# Sht5-V12P0_Jetson.net
KiCad netlist of a schematic drawn in Altium Designer
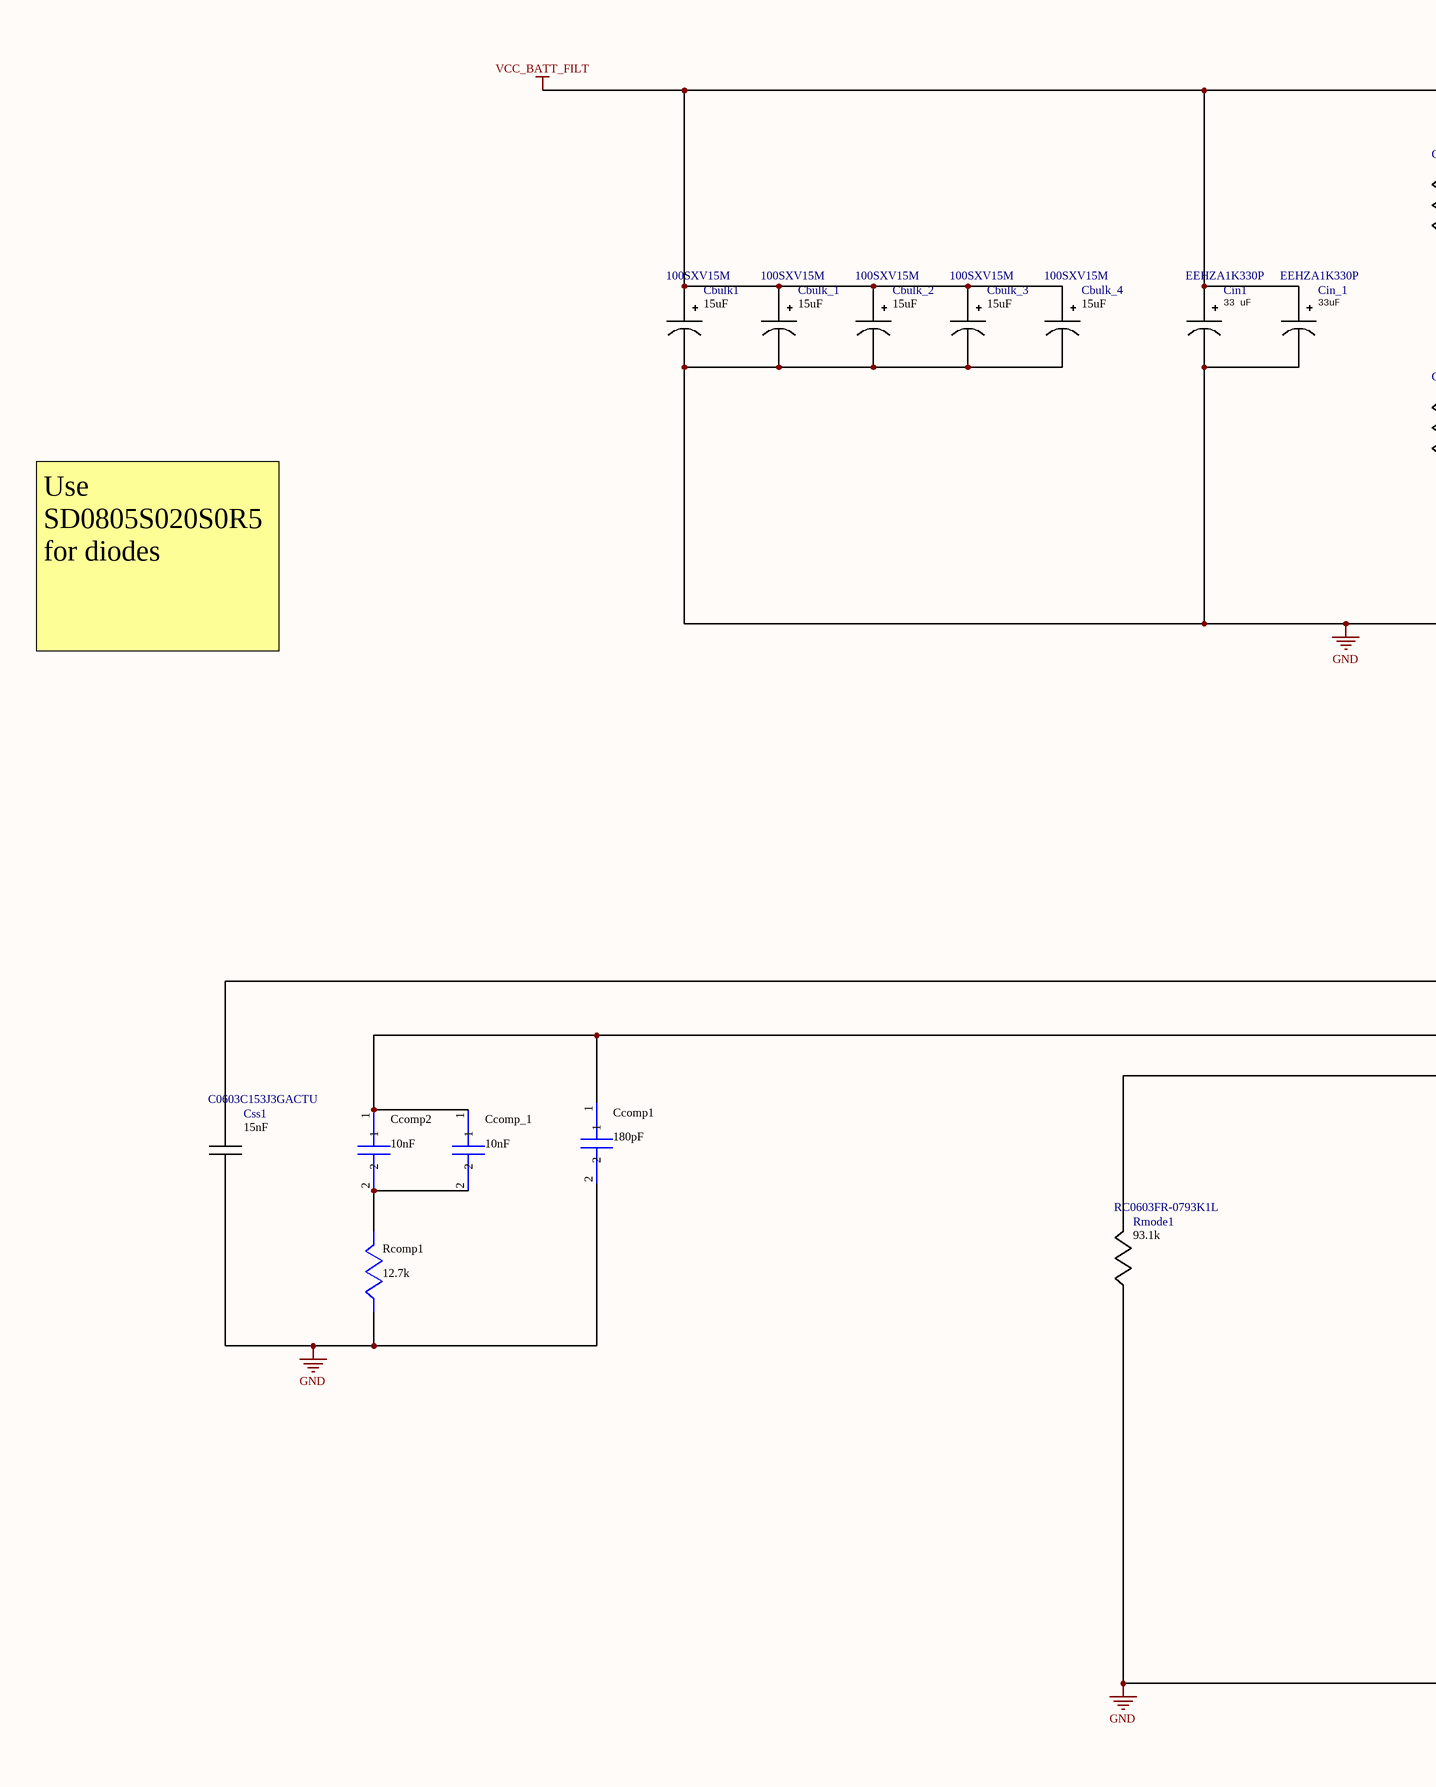
[diagram p0: Sht5-V12P0_Jetson.SchDoc, left]
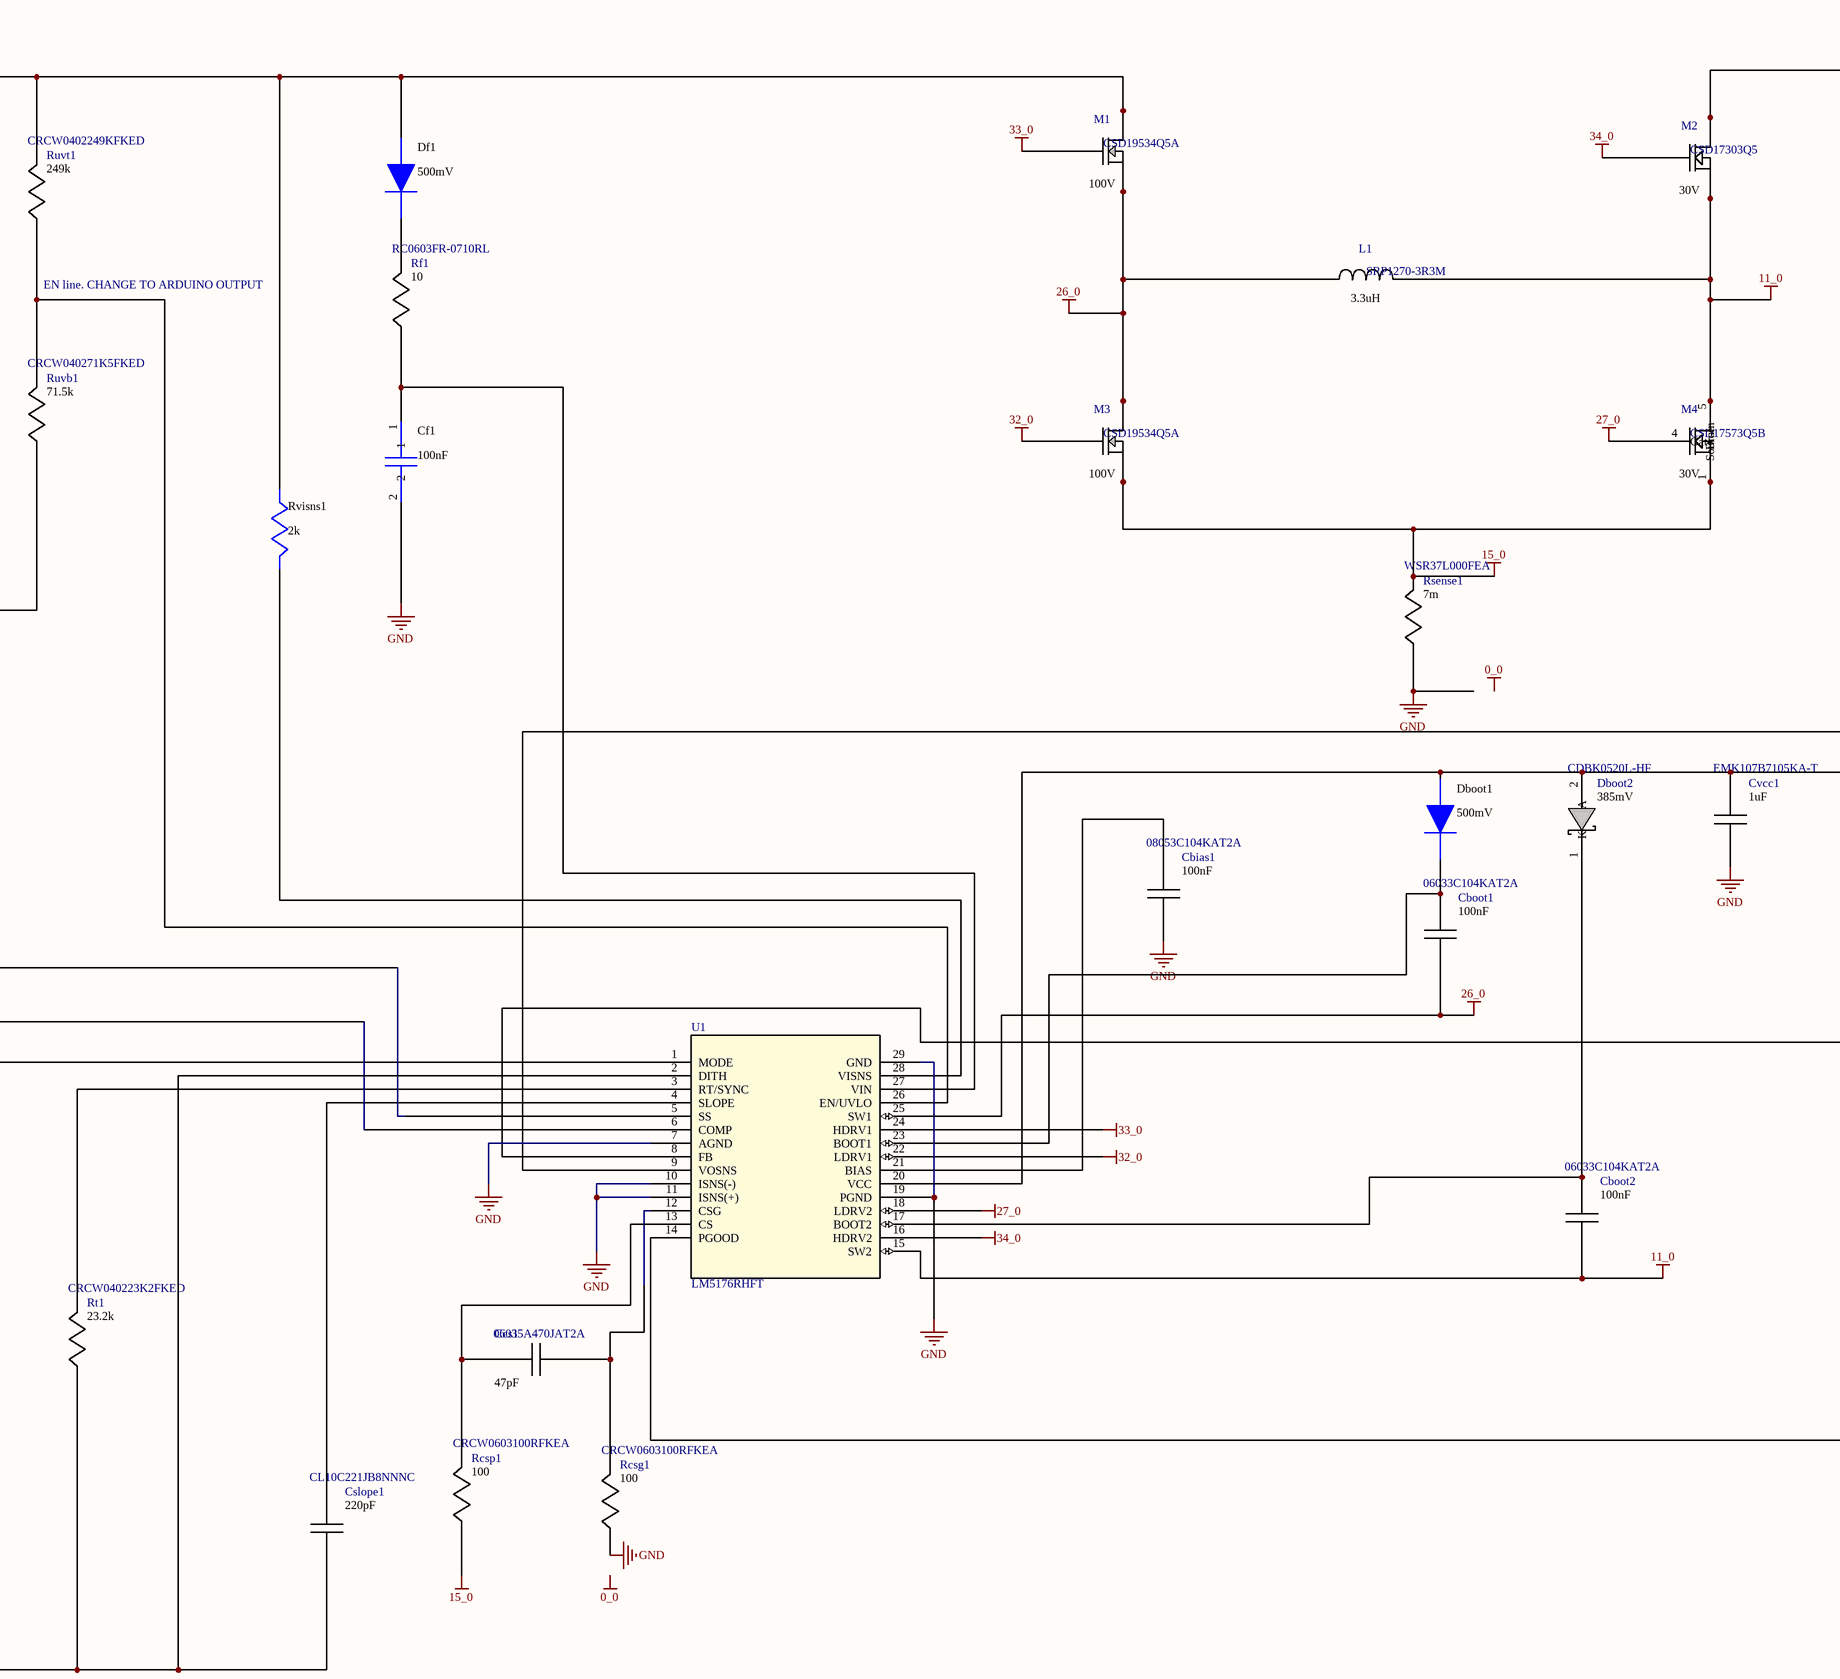
[diagram p1: Sht5-V12P0_Jetson.SchDoc, middle]
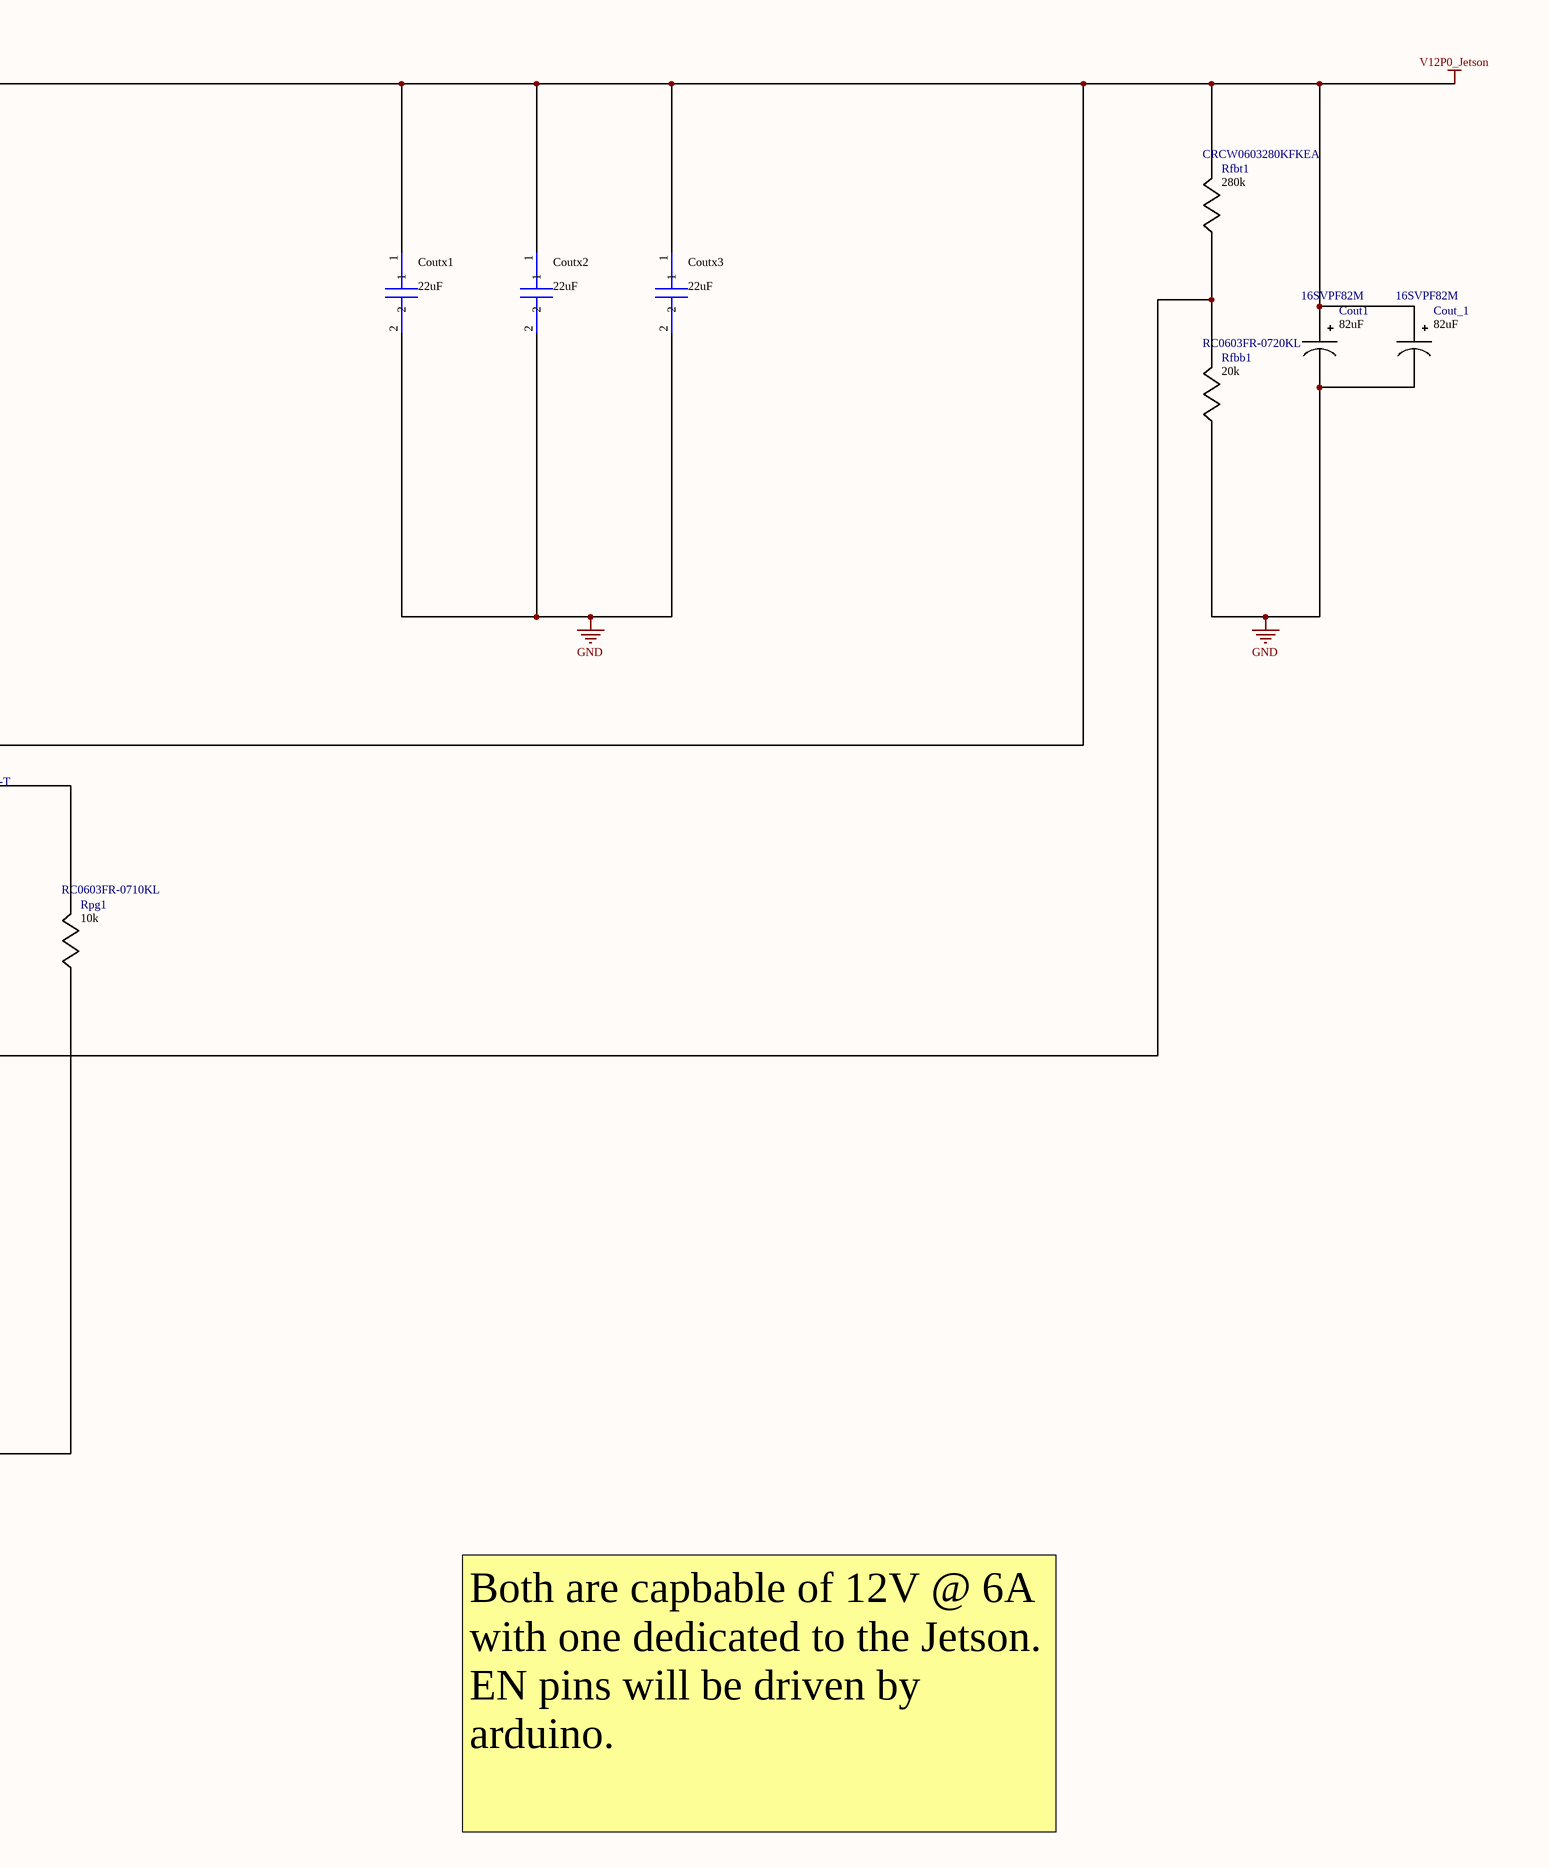
[diagram p2: Sht5-V12P0_Jetson.SchDoc, right]

(export (version "E")
  (design (tool "Eeschema 10.0.6"))
  (components
    (comp (ref "Cbias1")
      (value "08053C104KAT2A")
      (footprint "0805")
      (fields (field (name "ALTIUM_VALUE") "100nF"))
      (libsource (lib "TAUV-Lib") (part "08053C104KAT2A"))
    )
    (comp (ref "Cboot1")
      (value "06033C104KAT2A")
      (footprint "0603")
      (fields (field (name "ALTIUM_VALUE") "100nF"))
      (libsource (lib "TAUV-Lib") (part "06033C104KAT2A"))
    )
    (comp (ref "Cboot2")
      (value "06033C104KAT2A")
      (footprint "0603")
      (fields (field (name "ALTIUM_VALUE") "100nF"))
      (libsource (lib "TAUV-Lib") (part "06033C104KAT2A"))
    )
    (comp (ref "Cbulk1")
      (value "100SXV15M")
      (footprint "CAPSMT_62_E12")
      (fields (field (name "ALTIUM_VALUE") "15uF"))
      (libsource (lib "TAUV-Lib") (part "100SXV15M"))
    )
    (comp (ref "Cbulk_1")
      (value "100SXV15M")
      (footprint "CAPSMT_62_E12")
      (fields (field (name "ALTIUM_VALUE") "15uF"))
      (libsource (lib "TAUV-Lib") (part "100SXV15M"))
    )
    (comp (ref "Cbulk_2")
      (value "100SXV15M")
      (footprint "CAPSMT_62_E12")
      (fields (field (name "ALTIUM_VALUE") "15uF"))
      (libsource (lib "TAUV-Lib") (part "100SXV15M"))
    )
    (comp (ref "Cbulk_3")
      (value "100SXV15M")
      (footprint "CAPSMT_62_E12")
      (fields (field (name "ALTIUM_VALUE") "15uF"))
      (libsource (lib "TAUV-Lib") (part "100SXV15M"))
    )
    (comp (ref "Cbulk_4")
      (value "100SXV15M")
      (footprint "CAPSMT_62_E12")
      (fields (field (name "ALTIUM_VALUE") "15uF"))
      (libsource (lib "TAUV-Lib") (part "100SXV15M"))
    )
    (comp (ref "Ccomp1")
      (value "180pF")
      (footprint "0805")
      (description "C0805C181K5GACTU")
      (libsource (lib "TAUV-Lib") (part "Ccomp2"))
    )
    (comp (ref "Ccomp2")
      (value "10nF")
      (footprint "0402")
      (description "CGA2B3X7R1H103K0")
      (fields (field (name "MANUFACTURER PART NUMBER") "CGA2B3X7R1H103K050BB"))
      (libsource (lib "TAUV-Lib") (part "Ccomp"))
    )
    (comp (ref "Ccomp_1")
      (value "10nF")
      (footprint "0402")
      (description "CGA2B3X7R1H103K0")
      (fields (field (name "MANUFACTURER PART NUMBER") "CGA2B3X7R1H103K050BB"))
      (libsource (lib "TAUV-Lib") (part "Ccomp_2"))
    )
    (comp (ref "Ccs1")
      (value "06035A470JAT2A")
      (footprint "0603")
      (fields (field (name "ALTIUM_VALUE") "47pF"))
      (libsource (lib "TAUV-Lib") (part "06035A470JAT2A"))
    )
    (comp (ref "Cf1")
      (value "100nF")
      (footprint "0603")
      (description "CGA3E2X7R1H104K0")
      (fields (field (name "MANUFACTURER PART NUMBER") "CGA3E2X7R1H104K080AA"))
      (libsource (lib "TAUV-Lib") (part "Cf"))
    )
    (comp (ref "Cin1")
      (value "EEHZA1K330P")
      (footprint "SM_RADIAL_10BMM")
      (description "No Description Available")
      (fields
        (field (name "ALTIUM_VALUE") "33 uF")
        (field (name "COPYRIGHT") "Copyright (C) 2018 Accelerated Designs. All rights reserved")
      )
      (libsource (lib "TAUV-Lib") (part "EEHZA1K330P"))
    )
    (comp (ref "Cin_1")
      (value "EEHZA1K330P")
      (footprint "SM_RADIAL_10BMM")
      (description "No Description Available")
      (fields
        (field (name "ALTIUM_VALUE") "33uF")
        (field (name "COPYRIGHT") "Copyright (C) 2018 Accelerated Designs. All rights reserved")
      )
      (libsource (lib "TAUV-Lib") (part "EEHZA1K330P"))
    )
    (comp (ref "Cout1")
      (value "16SVPF82M")
      (footprint "CAPSMT_62_E61")
      (fields (field (name "ALTIUM_VALUE") "82uF"))
      (libsource (lib "TAUV-Lib") (part "16SVPF82M"))
    )
    (comp (ref "Coutx1")
      (value "22uF")
      (footprint "0805")
      (description "C2012X5R1V226M12")
      (fields (field (name "MANUFACTURER PART NUMBER") "C2012X5R1V226M125AC"))
      (libsource (lib "TAUV-Lib") (part "Coutx"))
    )
    (comp (ref "Coutx2")
      (value "22uF")
      (footprint "0805")
      (description "C2012X5R1V226M12")
      (fields (field (name "MANUFACTURER PART NUMBER") "C2012X5R1V226M125AC"))
      (libsource (lib "TAUV-Lib") (part "Coutx2"))
    )
    (comp (ref "Coutx3")
      (value "22uF")
      (footprint "0805")
      (description "C2012X5R1V226M12")
      (fields (field (name "MANUFACTURER PART NUMBER") "C2012X5R1V226M125AC"))
      (libsource (lib "TAUV-Lib") (part "Coutx3"))
    )
    (comp (ref "Cout_1")
      (value "16SVPF82M")
      (footprint "CAPSMT_62_E61")
      (fields (field (name "ALTIUM_VALUE") "82uF"))
      (libsource (lib "TAUV-Lib") (part "16SVPF82M"))
    )
    (comp (ref "Cslope1")
      (value "CL10C221JB8NNNC")
      (footprint "0603")
      (fields (field (name "ALTIUM_VALUE") "220pF"))
      (libsource (lib "TAUV-Lib") (part "CL10C221JB8NNNC"))
    )
    (comp (ref "Css1")
      (value "C0603C153J3GACTU")
      (footprint "0603")
      (fields (field (name "ALTIUM_VALUE") "15nF"))
      (libsource (lib "TAUV-Lib") (part "C0603C153J3GACTU"))
    )
    (comp (ref "Cvcc1")
      (value "EMK107B7105KA-T")
      (footprint "0603")
      (fields (field (name "ALTIUM_VALUE") "1uF"))
      (libsource (lib "TAUV-Lib") (part "EMK107B7105KA-T"))
    )
    (comp (ref "Dboot1")
      (value "500mV")
      (footprint "GEN_Diode")
      (description "CUSTOM1")
      (fields (field (name "MANUFACTURER PART NUMBER") "GENERIC_DIODE"))
      (libsource (lib "TAUV-Lib") (part "Dboot1"))
    )
    (comp (ref "Dboot2")
      (value "CDBK0520L-HF")
      (footprint "SOD-123F")
      (fields (field (name "ALTIUM_VALUE") "385mV"))
      (libsource (lib "TAUV-Lib") (part "CDBK0520L-HF"))
    )
    (comp (ref "Df1")
      (value "500mV")
      (footprint "GEN_Diode")
      (description "CUSTOM2")
      (fields (field (name "MANUFACTURER PART NUMBER") "GENERIC_DIODE"))
      (libsource (lib "TAUV-Lib") (part "Df"))
    )
    (comp (ref "L1")
      (value "SRP1270-3R3M")
      (footprint "SRP1270")
      (fields (field (name "ALTIUM_VALUE") "3.3uH"))
      (libsource (lib "TAUV-Lib") (part "SRP1270-3R3M"))
    )
    (comp (ref "M1")
      (value "CSD19534Q5A")
      (footprint "TRANS_NexFET_Q5A")
      (fields (field (name "ALTIUM_VALUE") "100V"))
      (libsource (lib "TAUV-Lib") (part "CSD19534Q5A"))
    )
    (comp (ref "M2")
      (value "CSD17303Q5")
      (footprint "TRANS_NexFET_Q5")
      (fields (field (name "ALTIUM_VALUE") "30V"))
      (libsource (lib "TAUV-Lib") (part "CSD17303Q5"))
    )
    (comp (ref "M3")
      (value "CSD19534Q5A")
      (footprint "TRANS_NexFET_Q5A")
      (fields (field (name "ALTIUM_VALUE") "100V"))
      (libsource (lib "TAUV-Lib") (part "CSD19534Q5A"))
    )
    (comp (ref "M4")
      (value "CSD17573Q5B")
      (footprint "DNK0008A")
      (description "CSD17573Q5B- Note out of stock, double check available subs")
      (fields (field (name "ALTIUM_VALUE") "30V"))
      (libsource (lib "TAUV-Lib") (part "CSD17573Q5B"))
    )
    (comp (ref "Rcomp1")
      (value "12.7k")
      (footprint "0402")
      (description "CRCW040212K7FKED")
      (libsource (lib "TAUV-Lib") (part "Rcomp"))
    )
    (comp (ref "Rcsg1")
      (value "CRCW0603100RFKEA")
      (footprint "0603")
      (fields (field (name "ALTIUM_VALUE") "100"))
      (libsource (lib "TAUV-Lib") (part "CRCW0603100RFKEA"))
    )
    (comp (ref "Rcsp1")
      (value "CRCW0603100RFKEA")
      (footprint "0603")
      (fields (field (name "ALTIUM_VALUE") "100"))
      (libsource (lib "TAUV-Lib") (part "CRCW0603100RFKEA"))
    )
    (comp (ref "Rf1")
      (value "RC0603FR-0710RL")
      (footprint "0603")
      (fields (field (name "ALTIUM_VALUE") "10"))
      (libsource (lib "TAUV-Lib") (part "RC0603FR-0710RL"))
    )
    (comp (ref "Rfbb1")
      (value "RC0603FR-0720KL")
      (footprint "0603")
      (fields (field (name "ALTIUM_VALUE") "20k"))
      (libsource (lib "TAUV-Lib") (part "RC0603FR-0720KL"))
    )
    (comp (ref "Rfbt1")
      (value "CRCW0603280KFKEA")
      (footprint "0603")
      (fields (field (name "ALTIUM_VALUE") "280k"))
      (libsource (lib "TAUV-Lib") (part "CRCW0603280KFKEA"))
    )
    (comp (ref "Rmode1")
      (value "RC0603FR-0793K1L")
      (footprint "0603")
      (fields (field (name "ALTIUM_VALUE") "93.1k"))
      (libsource (lib "TAUV-Lib") (part "RC0603FR-0793K1L"))
    )
    (comp (ref "Rpg1")
      (value "RC0603FR-0710KL")
      (footprint "0603")
      (fields (field (name "ALTIUM_VALUE") "10k"))
      (libsource (lib "TAUV-Lib") (part "RC0603FR-0710KL"))
    )
    (comp (ref "Rsense1")
      (value "WSR37L000FEA")
      (footprint "4527")
      (fields (field (name "ALTIUM_VALUE") "7m"))
      (libsource (lib "TAUV-Lib") (part "WSR37L000FEA"))
    )
    (comp (ref "Rt1")
      (value "CRCW040223K2FKED")
      (footprint "0402")
      (fields (field (name "ALTIUM_VALUE") "23.2k"))
      (libsource (lib "TAUV-Lib") (part "CRCW040223K2FKED"))
    )
    (comp (ref "Ruvb1")
      (value "CRCW040271K5FKED")
      (footprint "0402")
      (fields (field (name "ALTIUM_VALUE") "71.5k"))
      (libsource (lib "TAUV-Lib") (part "CRCW040271K5FKED"))
    )
    (comp (ref "Ruvt1")
      (value "CRCW0402249KFKED")
      (footprint "0402")
      (fields (field (name "ALTIUM_VALUE") "249k"))
      (libsource (lib "TAUV-Lib") (part "CRCW0402249KFKED"))
    )
    (comp (ref "Rvisns1")
      (value "2k")
      (footprint "0603")
      (description "CRCW06032K00FKEA")
      (libsource (lib "TAUV-Lib") (part "Rvisns"))
    )
    (comp (ref "U1")
      (value "LM5176RHFT")
      (footprint "VQFN_76RHFT_TEX")
      (description "No Description Available")
      (fields (field (name "COPYRIGHT") "Copyright (C) 2022 Ultra Librarian. All rights reserved."))
      (libsource (lib "TAUV-Lib") (part "LM5176RHFT"))
    )
  )
  (nets
    (net (code "2") (name "11_0") (class "Default")
      (node (ref "Cboot2") (pin "2") (pinfunction "2_2") (pintype "passive"))
      (node (ref "L1") (pin "2") (pinfunction "2_2") (pintype "passive"))
      (node (ref "M2") (pin "1") (pinfunction "Source_1") (pintype "passive"))
      (node (ref "M2") (pin "2") (pinfunction "Source_2") (pintype "passive"))
      (node (ref "M2") (pin "3") (pinfunction "Source_3") (pintype "passive"))
      (node (ref "M4") (pin "5") (pinfunction "Drain_5") (pintype "passive"))
      (node (ref "M4") (pin "6") (pinfunction "Drain_6") (pintype "passive"))
      (node (ref "M4") (pin "7") (pinfunction "Drain_7") (pintype "passive"))
      (node (ref "M4") (pin "8") (pinfunction "Drain_8") (pintype "passive"))
      (node (ref "M4") (pin "9") (pinfunction "Drain_9") (pintype "passive"))
      (node (ref "U1") (pin "15") (pinfunction "SW2_15") (pintype "bidirectional"))
    )
    (net (code "3") (name "15_0") (class "Default")
      (node (ref "M3") (pin "1") (pinfunction "Source_1") (pintype "passive"))
      (node (ref "M3") (pin "2") (pinfunction "Source_2") (pintype "passive"))
      (node (ref "M3") (pin "3") (pinfunction "Source_3") (pintype "passive"))
      (node (ref "M4") (pin "1") (pinfunction "Source_1") (pintype "passive"))
      (node (ref "M4") (pin "2") (pinfunction "Source_2") (pintype "passive"))
      (node (ref "M4") (pin "3") (pinfunction "Source_3") (pintype "passive"))
      (node (ref "Rcsp1") (pin "2") (pinfunction "2_2") (pintype "passive"))
      (node (ref "Rsense1") (pin "1") (pinfunction "1_1") (pintype "passive"))
    )
    (net (code "4") (name "26_0") (class "Default")
      (node (ref "Cboot1") (pin "2") (pinfunction "2_2") (pintype "passive"))
      (node (ref "L1") (pin "1") (pinfunction "1_1") (pintype "passive"))
      (node (ref "M1") (pin "1") (pinfunction "Source_1") (pintype "passive"))
      (node (ref "M1") (pin "2") (pinfunction "Source_2") (pintype "passive"))
      (node (ref "M1") (pin "3") (pinfunction "Source_3") (pintype "passive"))
      (node (ref "M3") (pin "5") (pinfunction "Drain_5") (pintype "passive"))
      (node (ref "M3") (pin "6") (pinfunction "Drain_6") (pintype "passive"))
      (node (ref "M3") (pin "7") (pinfunction "Drain_7") (pintype "passive"))
      (node (ref "M3") (pin "8") (pinfunction "Drain_8") (pintype "passive"))
      (node (ref "M3") (pin "9") (pinfunction "Drain_9") (pintype "passive"))
      (node (ref "U1") (pin "25") (pinfunction "SW1_25") (pintype "bidirectional"))
    )
    (net (code "5") (name "27_0") (class "Default")
      (node (ref "M4") (pin "4") (pinfunction "Gate_4") (pintype "passive"))
      (node (ref "U1") (pin "18") (pinfunction "LDRV2_18") (pintype "bidirectional"))
    )
    (net (code "6") (name "32_0") (class "Default")
      (node (ref "M3") (pin "4") (pinfunction "Gate_4") (pintype "passive"))
      (node (ref "U1") (pin "22") (pinfunction "LDRV1_22") (pintype "bidirectional"))
    )
    (net (code "7") (name "33_0") (class "Default")
      (node (ref "M1") (pin "4") (pinfunction "Gate_4") (pintype "passive"))
      (node (ref "U1") (pin "24") (pinfunction "HDRV1_24") (pintype "passive"))
    )
    (net (code "8") (name "34_0") (class "Default")
      (node (ref "M2") (pin "4") (pinfunction "Gate_4") (pintype "passive"))
      (node (ref "U1") (pin "16") (pinfunction "HDRV2_16") (pintype "passive"))
    )
    (net (code "9") (name "GND") (class "Default")
      (node (ref "Cbias1") (pin "2") (pinfunction "2_2") (pintype "passive"))
      (node (ref "Cbulk1") (pin "2") (pinfunction "-_2") (pintype "passive"))
      (node (ref "Cbulk_1") (pin "2") (pinfunction "-_2") (pintype "passive"))
      (node (ref "Cbulk_2") (pin "2") (pinfunction "-_2") (pintype "passive"))
      (node (ref "Cbulk_3") (pin "2") (pinfunction "-_2") (pintype "passive"))
      (node (ref "Cbulk_4") (pin "2") (pinfunction "-_2") (pintype "passive"))
      (node (ref "Ccomp1") (pin "2") (pinfunction "2_2") (pintype "passive"))
      (node (ref "Cf1") (pin "2") (pinfunction "2_2") (pintype "passive"))
      (node (ref "Cin1") (pin "2") (pinfunction "-_2") (pintype "passive"))
      (node (ref "Cin_1") (pin "2") (pinfunction "-_2") (pintype "passive"))
      (node (ref "Cout1") (pin "2") (pinfunction "-_2") (pintype "passive"))
      (node (ref "Cout_1") (pin "2") (pinfunction "-_2") (pintype "passive"))
      (node (ref "Coutx1") (pin "2") (pinfunction "2_2") (pintype "passive"))
      (node (ref "Coutx2") (pin "2") (pinfunction "2_2") (pintype "passive"))
      (node (ref "Coutx3") (pin "2") (pinfunction "2_2") (pintype "passive"))
      (node (ref "Cslope1") (pin "2") (pinfunction "2_2") (pintype "passive"))
      (node (ref "Css1") (pin "2") (pinfunction "2_2") (pintype "passive"))
      (node (ref "Cvcc1") (pin "2") (pinfunction "2_2") (pintype "passive"))
      (node (ref "Rcomp1") (pin "2") (pinfunction "2_2") (pintype "passive"))
      (node (ref "Rcsg1") (pin "2") (pinfunction "2_2") (pintype "passive"))
      (node (ref "Rfbb1") (pin "2") (pinfunction "2_2") (pintype "passive"))
      (node (ref "Rmode1") (pin "2") (pinfunction "2_2") (pintype "passive"))
      (node (ref "Rsense1") (pin "2") (pinfunction "2_2") (pintype "passive"))
      (node (ref "Rt1") (pin "2") (pinfunction "2_2") (pintype "passive"))
      (node (ref "Ruvb1") (pin "2") (pinfunction "2_2") (pintype "passive"))
      (node (ref "U1") (pin "10") (pinfunction "ISNS(-)_10") (pintype "passive"))
      (node (ref "U1") (pin "11") (pinfunction "ISNS(+)_11") (pintype "passive"))
      (node (ref "U1") (pin "19") (pinfunction "PGND_19") (pintype "passive"))
      (node (ref "U1") (pin "2") (pinfunction "DITH_2") (pintype "passive"))
      (node (ref "U1") (pin "29") (pinfunction "GND_29") (pintype "passive"))
      (node (ref "U1") (pin "7") (pinfunction "AGND_7") (pintype "passive"))
    )
    (net (code "10") (name "Net-(Ccomp2-Pad2)") (class "Default")
      (node (ref "Ccomp2") (pin "2") (pinfunction "2_2") (pintype "passive"))
      (node (ref "Ccomp_1") (pin "2") (pinfunction "2_2") (pintype "passive"))
      (node (ref "Rcomp1") (pin "1") (pinfunction "1_1") (pintype "passive"))
    )
    (net (code "11") (name "Net-(Dboot1-A)") (class "Default")
      (node (ref "Cvcc1") (pin "1") (pinfunction "1_1") (pintype "passive"))
      (node (ref "Dboot1") (pin "2") (pinfunction "A_2") (pintype "passive"))
      (node (ref "Dboot2") (pin "2") (pinfunction "A_2") (pintype "passive"))
      (node (ref "Rpg1") (pin "1") (pinfunction "1_1") (pintype "passive"))
      (node (ref "U1") (pin "20") (pinfunction "VCC_20") (pintype "power_in"))
    )
    (net (code "12") (name "Net-(Dboot1-K)") (class "Default")
      (node (ref "Cboot1") (pin "1") (pinfunction "1_1") (pintype "passive"))
      (node (ref "Dboot1") (pin "1") (pinfunction "K_1") (pintype "passive"))
      (node (ref "U1") (pin "23") (pinfunction "BOOT1_23") (pintype "bidirectional"))
    )
    (net (code "13") (name "Net-(Dboot2-K)") (class "Default")
      (node (ref "Cboot2") (pin "1") (pinfunction "1_1") (pintype "passive"))
      (node (ref "Dboot2") (pin "1") (pinfunction "K_1") (pintype "passive"))
      (node (ref "U1") (pin "17") (pinfunction "BOOT2_17") (pintype "bidirectional"))
    )
    (net (code "14") (name "Net-(Df1-K)") (class "Default")
      (node (ref "Df1") (pin "1") (pinfunction "K_1") (pintype "passive"))
      (node (ref "Rf1") (pin "1") (pinfunction "1_1") (pintype "passive"))
    )
    (net (code "15") (name "Net-(U1-BIAS)") (class "Default")
      (node (ref "Cbias1") (pin "1") (pinfunction "1_1") (pintype "passive"))
      (node (ref "U1") (pin "21") (pinfunction "BIAS_21") (pintype "passive"))
    )
    (net (code "16") (name "Net-(U1-COMP)") (class "Default")
      (node (ref "Ccomp1") (pin "1") (pinfunction "1_1") (pintype "passive"))
      (node (ref "Ccomp2") (pin "1") (pinfunction "1_1") (pintype "passive"))
      (node (ref "Ccomp_1") (pin "1") (pinfunction "1_1") (pintype "passive"))
      (node (ref "U1") (pin "6") (pinfunction "COMP_6") (pintype "passive"))
    )
    (net (code "17") (name "Net-(U1-CS)") (class "Default")
      (node (ref "Ccs1") (pin "1") (pinfunction "1_1") (pintype "passive"))
      (node (ref "Rcsp1") (pin "1") (pinfunction "1_1") (pintype "passive"))
      (node (ref "U1") (pin "13") (pinfunction "CS_13") (pintype "passive"))
    )
    (net (code "18") (name "Net-(U1-CSG)") (class "Default")
      (node (ref "Ccs1") (pin "2") (pinfunction "2_2") (pintype "passive"))
      (node (ref "Rcsg1") (pin "1") (pinfunction "1_1") (pintype "passive"))
      (node (ref "U1") (pin "12") (pinfunction "CSG_12") (pintype "passive"))
    )
    (net (code "19") (name "Net-(U1-EN{slash}UVLO)") (class "Default")
      (node (ref "Ruvb1") (pin "1") (pinfunction "1_1") (pintype "passive"))
      (node (ref "Ruvt1") (pin "2") (pinfunction "2_2") (pintype "passive"))
      (node (ref "U1") (pin "26") (pinfunction "EN/UVLO_26") (pintype "passive"))
    )
    (net (code "20") (name "Net-(U1-FB)") (class "Default")
      (node (ref "Rfbb1") (pin "1") (pinfunction "1_1") (pintype "passive"))
      (node (ref "Rfbt1") (pin "2") (pinfunction "2_2") (pintype "passive"))
      (node (ref "U1") (pin "8") (pinfunction "FB_8") (pintype "passive"))
    )
    (net (code "21") (name "Net-(U1-MODE)") (class "Default")
      (node (ref "Rmode1") (pin "1") (pinfunction "1_1") (pintype "passive"))
      (node (ref "U1") (pin "1") (pinfunction "MODE_1") (pintype "passive"))
    )
    (net (code "22") (name "Net-(U1-PGOOD)") (class "Default")
      (node (ref "Rpg1") (pin "2") (pinfunction "2_2") (pintype "passive"))
      (node (ref "U1") (pin "14") (pinfunction "PGOOD_14") (pintype "power_in"))
    )
    (net (code "23") (name "Net-(U1-RT{slash}SYNC)") (class "Default")
      (node (ref "Rt1") (pin "1") (pinfunction "1_1") (pintype "passive"))
      (node (ref "U1") (pin "3") (pinfunction "RT/SYNC_3") (pintype "passive"))
    )
    (net (code "24") (name "Net-(U1-SLOPE)") (class "Default")
      (node (ref "Cslope1") (pin "1") (pinfunction "1_1") (pintype "passive"))
      (node (ref "U1") (pin "4") (pinfunction "SLOPE_4") (pintype "passive"))
    )
    (net (code "25") (name "Net-(U1-SS)") (class "Default")
      (node (ref "Css1") (pin "1") (pinfunction "1_1") (pintype "passive"))
      (node (ref "U1") (pin "5") (pinfunction "SS_5") (pintype "passive"))
    )
    (net (code "26") (name "Net-(U1-VIN)") (class "Default")
      (node (ref "Cf1") (pin "1") (pinfunction "1_1") (pintype "passive"))
      (node (ref "Rf1") (pin "2") (pinfunction "2_2") (pintype "passive"))
      (node (ref "U1") (pin "27") (pinfunction "VIN_27") (pintype "passive"))
    )
    (net (code "27") (name "Net-(U1-VISNS)") (class "Default")
      (node (ref "Rvisns1") (pin "1") (pinfunction "1_1") (pintype "passive"))
      (node (ref "U1") (pin "28") (pinfunction "VISNS_28") (pintype "passive"))
    )
    (net (code "28") (name "V12P0_Jetson") (class "Default")
      (node (ref "Cout1") (pin "1") (pinfunction "+_1") (pintype "passive"))
      (node (ref "Cout_1") (pin "1") (pinfunction "+_1") (pintype "passive"))
      (node (ref "Coutx1") (pin "1") (pinfunction "1_1") (pintype "passive"))
      (node (ref "Coutx2") (pin "1") (pinfunction "1_1") (pintype "passive"))
      (node (ref "Coutx3") (pin "1") (pinfunction "1_1") (pintype "passive"))
      (node (ref "M2") (pin "5") (pinfunction "Drain_5") (pintype "passive"))
      (node (ref "M2") (pin "6") (pinfunction "Drain_6") (pintype "passive"))
      (node (ref "M2") (pin "7") (pinfunction "Drain_7") (pintype "passive"))
      (node (ref "M2") (pin "8") (pinfunction "Drain_8") (pintype "passive"))
      (node (ref "M2") (pin "9") (pinfunction "Drain_9") (pintype "passive"))
      (node (ref "Rfbt1") (pin "1") (pinfunction "1_1") (pintype "passive"))
      (node (ref "U1") (pin "9") (pinfunction "VOSNS_9") (pintype "passive"))
    )
    (net (code "29") (name "VCC_BATT_FILT") (class "Default")
      (node (ref "Cbulk1") (pin "1") (pinfunction "+_1") (pintype "passive"))
      (node (ref "Cbulk_1") (pin "1") (pinfunction "+_1") (pintype "passive"))
      (node (ref "Cbulk_2") (pin "1") (pinfunction "+_1") (pintype "passive"))
      (node (ref "Cbulk_3") (pin "1") (pinfunction "+_1") (pintype "passive"))
      (node (ref "Cbulk_4") (pin "1") (pinfunction "+_1") (pintype "passive"))
      (node (ref "Cin1") (pin "1") (pinfunction "+_1") (pintype "passive"))
      (node (ref "Cin_1") (pin "1") (pinfunction "+_1") (pintype "passive"))
      (node (ref "Df1") (pin "2") (pinfunction "A_2") (pintype "passive"))
      (node (ref "M1") (pin "5") (pinfunction "Drain_5") (pintype "passive"))
      (node (ref "M1") (pin "6") (pinfunction "Drain_6") (pintype "passive"))
      (node (ref "M1") (pin "7") (pinfunction "Drain_7") (pintype "passive"))
      (node (ref "M1") (pin "8") (pinfunction "Drain_8") (pintype "passive"))
      (node (ref "M1") (pin "9") (pinfunction "Drain_9") (pintype "passive"))
      (node (ref "Ruvt1") (pin "1") (pinfunction "1_1") (pintype "passive"))
      (node (ref "Rvisns1") (pin "2") (pinfunction "2_2") (pintype "passive"))
    )
  )
)
